# xmod_A.net
KiCad netlist of a schematic drawn in EAGLE
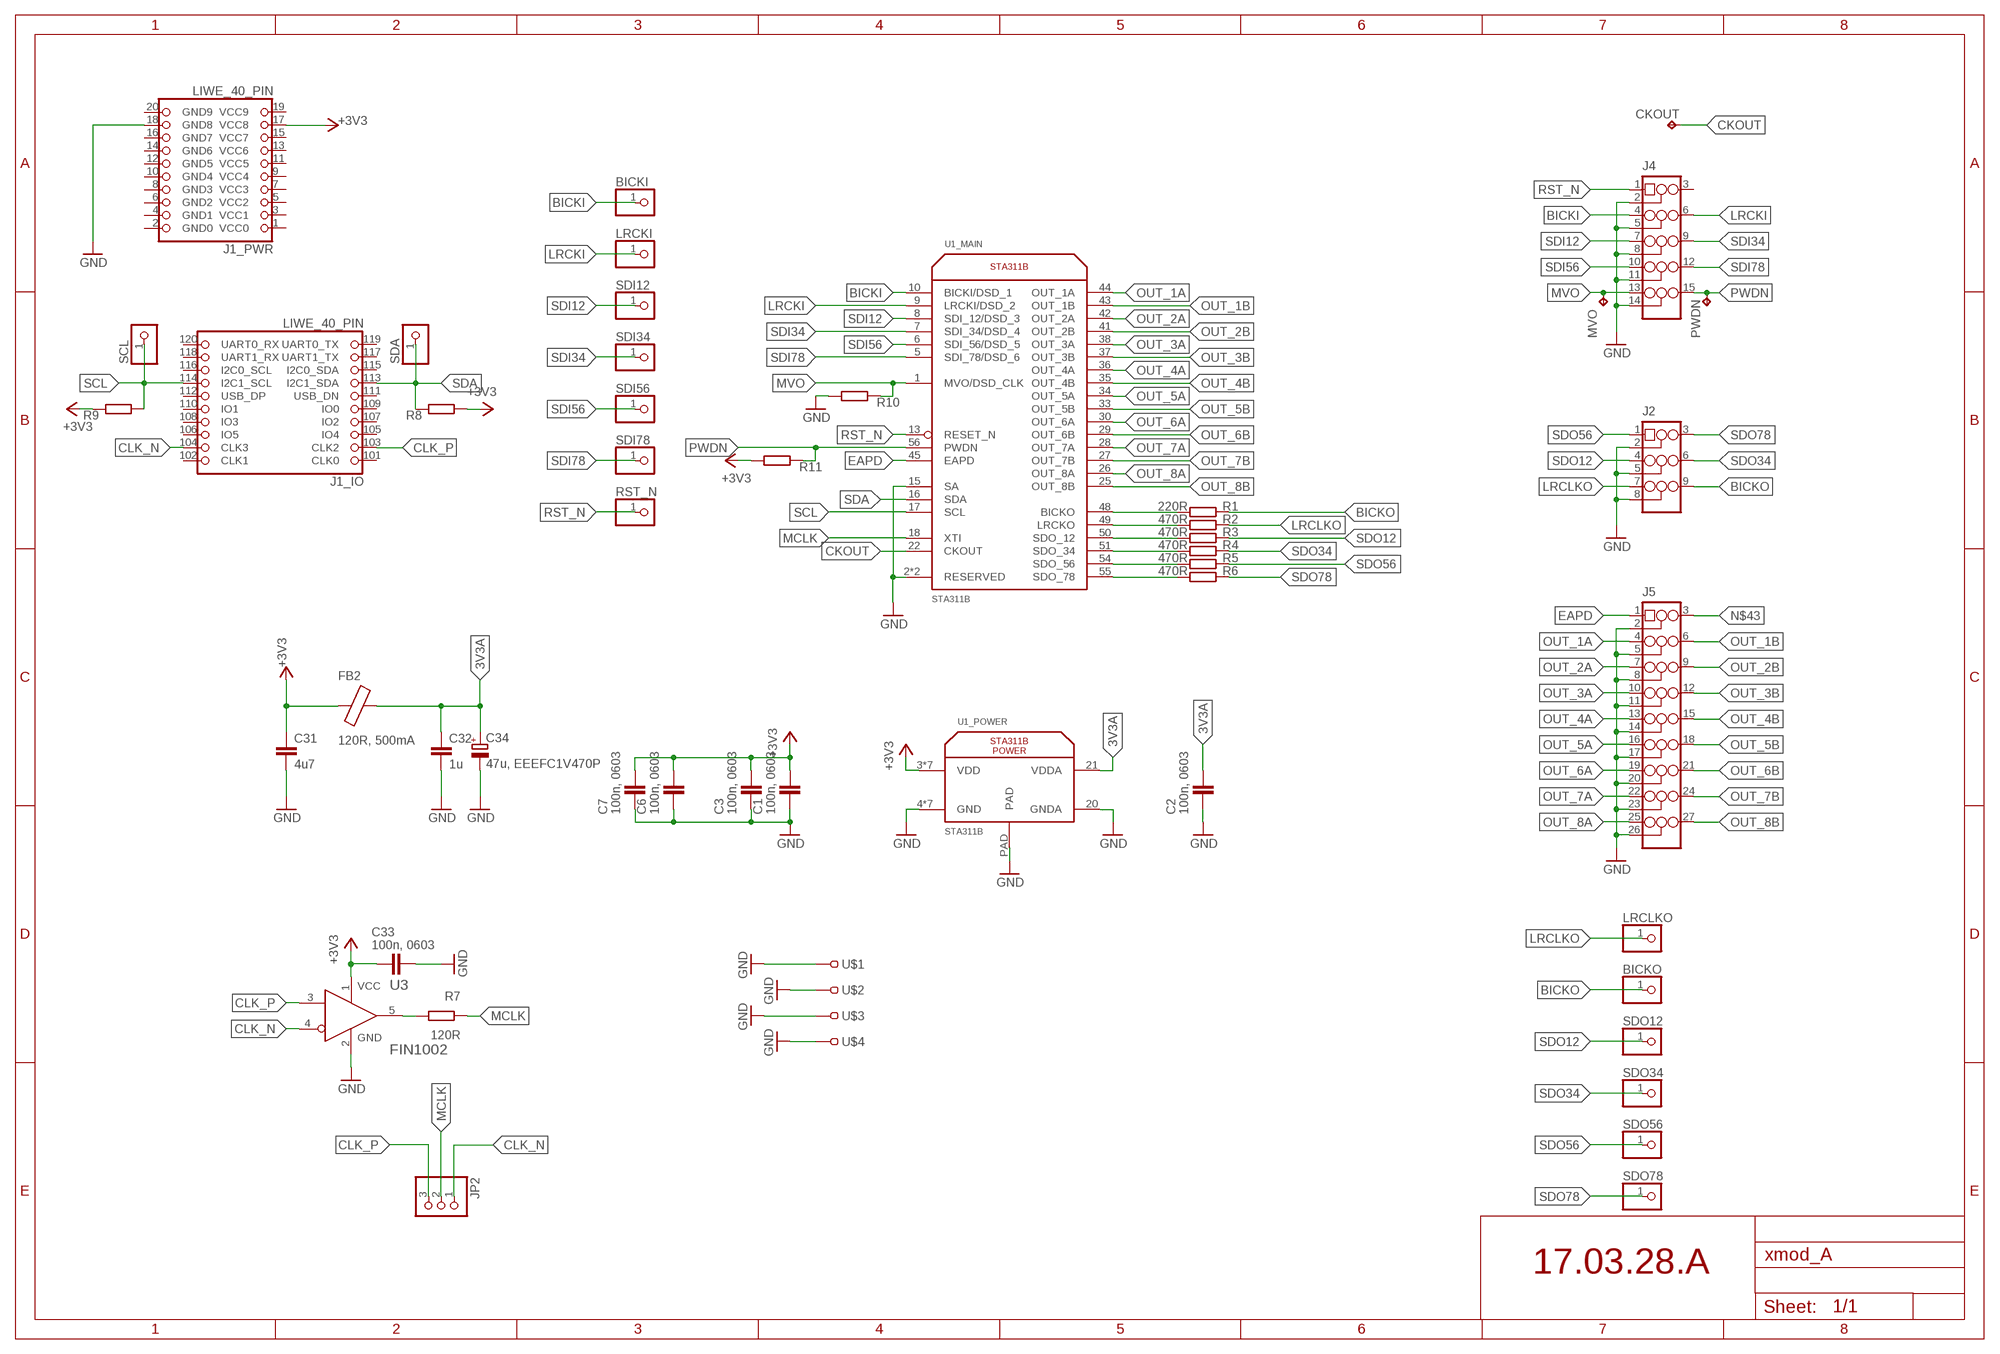
[diagram p0: schematic, sheet 1]

(export (version "E")
  (design (tool "Eeschema 10.0.6"))
  (components
    (comp (ref "BICKI")
      (value "PINHD-1X1")
      (footprint "eagle-import:1X01")
      (libsource (lib "eagle-import") (part "PINHD-1X1"))
    )
    (comp (ref "BICKO")
      (value "PINHD-1X1")
      (footprint "eagle-import:1X01")
      (libsource (lib "eagle-import") (part "PINHD-1X1"))
    )
    (comp (ref "C1")
      (value "100n, 0603")
      (footprint "eagle-import:C0603")
      (libsource (lib "eagle-import") (part "C-EUC0603"))
    )
    (comp (ref "C2")
      (value "100n, 0603")
      (footprint "eagle-import:C0603")
      (libsource (lib "eagle-import") (part "C-EUC0603"))
    )
    (comp (ref "C3")
      (value "100n, 0603")
      (footprint "eagle-import:C0603")
      (libsource (lib "eagle-import") (part "C-EUC0603"))
    )
    (comp (ref "C6")
      (value "100n, 0603")
      (footprint "eagle-import:C0603")
      (libsource (lib "eagle-import") (part "C-EUC0603"))
    )
    (comp (ref "C7")
      (value "100n, 0603")
      (footprint "eagle-import:C0603")
      (libsource (lib "eagle-import") (part "C-EUC0603"))
    )
    (comp (ref "C31")
      (value "4u7")
      (footprint "eagle-import:C0603K")
      (libsource (lib "eagle-import") (part "C-EUC0603K"))
    )
    (comp (ref "C32")
      (value "1u")
      (footprint "eagle-import:C0603K")
      (libsource (lib "eagle-import") (part "C-EUC0603K"))
    )
    (comp (ref "C33")
      (value "100n, 0603")
      (footprint "eagle-import:C0603")
      (libsource (lib "eagle-import") (part "C-EUC0603"))
    )
    (comp (ref "C34")
      (value "47u, EEEFC1V470P")
      (footprint "eagle-import:EEE-FC1V470P")
      (libsource (lib "eagle-import") (part "C-POL_E"))
    )
    (comp (ref "CKOUT")
      (value "TPTP14R")
      (footprint "eagle-import:TP14R")
      (libsource (lib "eagle-import") (part "TPTP14R"))
    )
    (comp (ref "FB2")
      (value "120R, 500mA")
      (footprint "eagle-import:L0603")
      (libsource (lib "eagle-import") (part "FB_0603"))
    )
    (comp (ref "J1")
      (value "LIWE_40_PIN")
      (footprint "eagle-import:LIWE_40_PIN_8X8")
      (libsource (lib "eagle-import") (part "LIWE_40_PIN"))
    )
    (comp (ref "J2")
      (value "PINHD-3X3/90")
      (footprint "eagle-import:3X03_90")
      (libsource (lib "eagle-import") (part "PINHD-3X3/90"))
    )
    (comp (ref "J4")
      (value "PINHD-3X5/90")
      (footprint "eagle-import:3X05_90")
      (libsource (lib "eagle-import") (part "PINHD-3X5/90"))
    )
    (comp (ref "J5")
      (value "PINHD-3X9/90")
      (footprint "eagle-import:3X9_90")
      (libsource (lib "eagle-import") (part "PINHD-3X9/90"))
    )
    (comp (ref "JP2")
      (value "PINHD-1X3")
      (footprint "eagle-import:1X03")
      (libsource (lib "eagle-import") (part "PINHD-1X3"))
    )
    (comp (ref "LRCKI")
      (value "PINHD-1X1")
      (footprint "eagle-import:1X01")
      (libsource (lib "eagle-import") (part "PINHD-1X1"))
    )
    (comp (ref "LRCLKO")
      (value "PINHD-1X1")
      (footprint "eagle-import:1X01")
      (libsource (lib "eagle-import") (part "PINHD-1X1"))
    )
    (comp (ref "MVO")
      (value "TPTP14R")
      (footprint "eagle-import:TP14R")
      (libsource (lib "eagle-import") (part "TPTP14R"))
    )
    (comp (ref "PWDN")
      (value "TPTP14R")
      (footprint "eagle-import:TP14R")
      (libsource (lib "eagle-import") (part "TPTP14R"))
    )
    (comp (ref "R1")
      (value "220R")
      (footprint "eagle-import:R0603")
      (libsource (lib "eagle-import") (part "R-EU_R0603"))
    )
    (comp (ref "R2")
      (value "470R")
      (footprint "eagle-import:R0603")
      (libsource (lib "eagle-import") (part "R-EU_R0603"))
    )
    (comp (ref "R3")
      (value "470R")
      (footprint "eagle-import:R0603")
      (libsource (lib "eagle-import") (part "R-EU_R0603"))
    )
    (comp (ref "R4")
      (value "470R")
      (footprint "eagle-import:R0603")
      (libsource (lib "eagle-import") (part "R-EU_R0603"))
    )
    (comp (ref "R5")
      (value "470R")
      (footprint "eagle-import:R0603")
      (libsource (lib "eagle-import") (part "R-EU_R0603"))
    )
    (comp (ref "R6")
      (value "470R")
      (footprint "eagle-import:R0603")
      (libsource (lib "eagle-import") (part "R-EU_R0603"))
    )
    (comp (ref "R7")
      (value "120R")
      (footprint "eagle-import:R0603")
      (libsource (lib "eagle-import") (part "R-EU_R0603"))
    )
    (comp (ref "R8")
      (value "R-EU_R0603")
      (footprint "eagle-import:R0603")
      (libsource (lib "eagle-import") (part "R-EU_R0603"))
    )
    (comp (ref "R9")
      (value "R-EU_R0603")
      (footprint "eagle-import:R0603")
      (libsource (lib "eagle-import") (part "R-EU_R0603"))
    )
    (comp (ref "R10")
      (value "R-EU_R0603")
      (footprint "eagle-import:R0603")
      (libsource (lib "eagle-import") (part "R-EU_R0603"))
    )
    (comp (ref "R11")
      (value "R-EU_R0603")
      (footprint "eagle-import:R0603")
      (libsource (lib "eagle-import") (part "R-EU_R0603"))
    )
    (comp (ref "RST_N")
      (value "PINHD-1X1")
      (footprint "eagle-import:1X01")
      (libsource (lib "eagle-import") (part "PINHD-1X1"))
    )
    (comp (ref "SCL")
      (value "PINHD-1X1")
      (footprint "eagle-import:1X01")
      (libsource (lib "eagle-import") (part "PINHD-1X1"))
    )
    (comp (ref "SDA")
      (value "PINHD-1X1")
      (footprint "eagle-import:1X01")
      (libsource (lib "eagle-import") (part "PINHD-1X1"))
    )
    (comp (ref "SDI12")
      (value "PINHD-1X1")
      (footprint "eagle-import:1X01")
      (libsource (lib "eagle-import") (part "PINHD-1X1"))
    )
    (comp (ref "SDI34")
      (value "PINHD-1X1")
      (footprint "eagle-import:1X01")
      (libsource (lib "eagle-import") (part "PINHD-1X1"))
    )
    (comp (ref "SDI56")
      (value "PINHD-1X1")
      (footprint "eagle-import:1X01")
      (libsource (lib "eagle-import") (part "PINHD-1X1"))
    )
    (comp (ref "SDI78")
      (value "PINHD-1X1")
      (footprint "eagle-import:1X01")
      (libsource (lib "eagle-import") (part "PINHD-1X1"))
    )
    (comp (ref "SDO12")
      (value "PINHD-1X1")
      (footprint "eagle-import:1X01")
      (libsource (lib "eagle-import") (part "PINHD-1X1"))
    )
    (comp (ref "SDO34")
      (value "PINHD-1X1")
      (footprint "eagle-import:1X01")
      (libsource (lib "eagle-import") (part "PINHD-1X1"))
    )
    (comp (ref "SDO56")
      (value "PINHD-1X1")
      (footprint "eagle-import:1X01")
      (libsource (lib "eagle-import") (part "PINHD-1X1"))
    )
    (comp (ref "SDO78")
      (value "PINHD-1X1")
      (footprint "eagle-import:1X01")
      (libsource (lib "eagle-import") (part "PINHD-1X1"))
    )
    (comp (ref "U$1")
      (value "TEST-22-MULTICOMP")
      (footprint "eagle-import:TEST_1MM")
      (libsource (lib "eagle-import") (part "TEST-22-MULTICOMP"))
    )
    (comp (ref "U$2")
      (value "TEST-22-MULTICOMP")
      (footprint "eagle-import:TEST_1MM")
      (libsource (lib "eagle-import") (part "TEST-22-MULTICOMP"))
    )
    (comp (ref "U$3")
      (value "TEST-22-MULTICOMP")
      (footprint "eagle-import:TEST_1MM")
      (libsource (lib "eagle-import") (part "TEST-22-MULTICOMP"))
    )
    (comp (ref "U$4")
      (value "TEST-22-MULTICOMP")
      (footprint "eagle-import:TEST_1MM")
      (libsource (lib "eagle-import") (part "TEST-22-MULTICOMP"))
    )
    (comp (ref "U1")
      (value "STA311B")
      (footprint "eagle-import:VFQFPN_56_8X8")
      (libsource (lib "eagle-import") (part "STA311B"))
    )
    (comp (ref "U3")
      (value "FIN1002")
      (footprint "eagle-import:SOT95P280X140-5N")
      (libsource (lib "eagle-import") (part "FIN1002"))
    )
  )
  (nets
    (net (code "1") (name "+3V3") (class "Default")
      (node (ref "C1") (pin "1") (pinfunction "1_1") (pintype "passive"))
      (node (ref "C3") (pin "1") (pinfunction "1_1") (pintype "passive"))
      (node (ref "C31") (pin "1") (pinfunction "1_1") (pintype "passive"))
      (node (ref "C33") (pin "2") (pinfunction "2_2") (pintype "passive"))
      (node (ref "C6") (pin "1") (pinfunction "1_1") (pintype "passive"))
      (node (ref "C7") (pin "1") (pinfunction "1_1") (pintype "passive"))
      (node (ref "FB2") (pin "2") (pinfunction "P$2_2") (pintype "bidirectional"))
      (node (ref "J1") (pin "17") (pinfunction "VCC8_17") (pintype "passive"))
      (node (ref "R11") (pin "2") (pinfunction "2_2") (pintype "passive"))
      (node (ref "R8") (pin "1") (pinfunction "1_1") (pintype "passive"))
      (node (ref "R9") (pin "2") (pinfunction "2_2") (pintype "passive"))
      (node (ref "U1") (pin "11") (pinfunction "VDD_11") (pintype "bidirectional"))
      (node (ref "U1") (pin "24") (pinfunction "VDD_24") (pintype "bidirectional"))
      (node (ref "U1") (pin "3") (pinfunction "VDD_3") (pintype "bidirectional"))
      (node (ref "U1") (pin "31") (pinfunction "VDD_31") (pintype "bidirectional"))
      (node (ref "U1") (pin "39") (pinfunction "VDD_39") (pintype "bidirectional"))
      (node (ref "U1") (pin "46") (pinfunction "VDD_46") (pintype "bidirectional"))
      (node (ref "U1") (pin "52") (pinfunction "VDD_52") (pintype "bidirectional"))
      (node (ref "U3") (pin "1") (pinfunction "VCC_1") (pintype "power_in"))
    )
    (net (code "2") (name "3V3A") (class "Default")
      (node (ref "C2") (pin "1") (pinfunction "1_1") (pintype "passive"))
      (node (ref "C32") (pin "1") (pinfunction "1_1") (pintype "passive"))
      (node (ref "C34") (pin "1") (pinfunction "+_1") (pintype "passive"))
      (node (ref "FB2") (pin "1") (pinfunction "P$1_1") (pintype "bidirectional"))
      (node (ref "U1") (pin "21") (pinfunction "VDDA_21") (pintype "bidirectional"))
    )
    (net (code "3") (name "BICKI") (class "Default")
      (node (ref "BICKI") (pin "1") (pinfunction "1_1") (pintype "passive"))
      (node (ref "J4") (pin "4") (pinfunction "4_4") (pintype "passive"))
      (node (ref "U1") (pin "10") (pinfunction "BICKI/DSD_1_10") (pintype "bidirectional"))
    )
    (net (code "4") (name "BICKO") (class "Default")
      (node (ref "BICKO") (pin "1") (pinfunction "1_1") (pintype "passive"))
      (node (ref "J2") (pin "9") (pinfunction "9_9") (pintype "passive"))
      (node (ref "R1") (pin "2") (pinfunction "2_2") (pintype "passive"))
    )
    (net (code "5") (name "CKOUT") (class "Default")
      (node (ref "CKOUT") (pin "TP") (pinfunction "TP_TP") (pintype "input"))
      (node (ref "U1") (pin "22") (pinfunction "CKOUT_22") (pintype "bidirectional"))
    )
    (net (code "6") (name "CLK_N") (class "Default")
      (node (ref "J1") (pin "104") (pinfunction "CLK3_104") (pintype "passive"))
      (node (ref "JP2") (pin "1") (pinfunction "1_1") (pintype "passive"))
      (node (ref "U3") (pin "4") (pinfunction "RIN-_4") (pintype "input"))
    )
    (net (code "7") (name "CLK_P") (class "Default")
      (node (ref "J1") (pin "103") (pinfunction "CLK2_103") (pintype "passive"))
      (node (ref "JP2") (pin "3") (pinfunction "3_3") (pintype "passive"))
      (node (ref "U3") (pin "3") (pinfunction "RIN+_3") (pintype "input"))
    )
    (net (code "8") (name "EAPD") (class "Default")
      (node (ref "J5") (pin "1") (pinfunction "1_1") (pintype "passive"))
      (node (ref "U1") (pin "45") (pinfunction "EAPD_45") (pintype "bidirectional"))
    )
    (net (code "9") (name "GND") (class "Default")
      (node (ref "C1") (pin "2") (pinfunction "2_2") (pintype "passive"))
      (node (ref "C2") (pin "2") (pinfunction "2_2") (pintype "passive"))
      (node (ref "C3") (pin "2") (pinfunction "2_2") (pintype "passive"))
      (node (ref "C31") (pin "2") (pinfunction "2_2") (pintype "passive"))
      (node (ref "C32") (pin "2") (pinfunction "2_2") (pintype "passive"))
      (node (ref "C33") (pin "1") (pinfunction "1_1") (pintype "passive"))
      (node (ref "C34") (pin "2") (pinfunction "-_2") (pintype "passive"))
      (node (ref "C6") (pin "2") (pinfunction "2_2") (pintype "passive"))
      (node (ref "C7") (pin "2") (pinfunction "2_2") (pintype "passive"))
      (node (ref "J1") (pin "18") (pinfunction "GND8_18") (pintype "passive"))
      (node (ref "J2") (pin "2") (pinfunction "2_2") (pintype "passive"))
      (node (ref "J2") (pin "5") (pinfunction "5_5") (pintype "passive"))
      (node (ref "J2") (pin "8") (pinfunction "8_8") (pintype "passive"))
      (node (ref "J4") (pin "11") (pinfunction "11_11") (pintype "passive"))
      (node (ref "J4") (pin "14") (pinfunction "14_14") (pintype "passive"))
      (node (ref "J4") (pin "2") (pinfunction "2_2") (pintype "passive"))
      (node (ref "J4") (pin "5") (pinfunction "5_5") (pintype "passive"))
      (node (ref "J4") (pin "8") (pinfunction "8_8") (pintype "passive"))
      (node (ref "J5") (pin "11") (pinfunction "11_11") (pintype "passive"))
      (node (ref "J5") (pin "14") (pinfunction "14_14") (pintype "passive"))
      (node (ref "J5") (pin "17") (pinfunction "17_17") (pintype "passive"))
      (node (ref "J5") (pin "2") (pinfunction "2_2") (pintype "passive"))
      (node (ref "J5") (pin "20") (pinfunction "20_20") (pintype "passive"))
      (node (ref "J5") (pin "23") (pinfunction "23_23") (pintype "passive"))
      (node (ref "J5") (pin "26") (pinfunction "26_26") (pintype "passive"))
      (node (ref "J5") (pin "5") (pinfunction "5_5") (pintype "passive"))
      (node (ref "J5") (pin "8") (pinfunction "8_8") (pintype "passive"))
      (node (ref "R10") (pin "2") (pinfunction "2_2") (pintype "passive"))
      (node (ref "U$1") (pin "1") (pinfunction "1_1") (pintype "passive"))
      (node (ref "U$2") (pin "1") (pinfunction "1_1") (pintype "passive"))
      (node (ref "U$3") (pin "1") (pinfunction "1_1") (pintype "passive"))
      (node (ref "U$4") (pin "1") (pinfunction "1_1") (pintype "passive"))
      (node (ref "U1") (pin "12") (pinfunction "GND_12") (pintype "bidirectional"))
      (node (ref "U1") (pin "14") (pinfunction "RESERVED_14") (pintype "bidirectional"))
      (node (ref "U1") (pin "15") (pinfunction "SA_15") (pintype "bidirectional"))
      (node (ref "U1") (pin "2") (pinfunction "RESERVED_2") (pintype "bidirectional"))
      (node (ref "U1") (pin "20") (pinfunction "GNDA_20") (pintype "bidirectional"))
      (node (ref "U1") (pin "23") (pinfunction "GND_23") (pintype "bidirectional"))
      (node (ref "U1") (pin "32") (pinfunction "GND_32") (pintype "bidirectional"))
      (node (ref "U1") (pin "4") (pinfunction "GND_4") (pintype "bidirectional"))
      (node (ref "U1") (pin "40") (pinfunction "GND_40") (pintype "bidirectional"))
      (node (ref "U1") (pin "47") (pinfunction "GND_47") (pintype "bidirectional"))
      (node (ref "U1") (pin "53") (pinfunction "GND_53") (pintype "bidirectional"))
      (node (ref "U1") (pin "PAD") (pinfunction "PAD_PAD") (pintype "bidirectional"))
      (node (ref "U3") (pin "2") (pinfunction "GND_2") (pintype "passive"))
    )
    (net (code "10") (name "LRCKI") (class "Default")
      (node (ref "J4") (pin "6") (pinfunction "6_6") (pintype "passive"))
      (node (ref "LRCKI") (pin "1") (pinfunction "1_1") (pintype "passive"))
      (node (ref "U1") (pin "9") (pinfunction "LRCKI/DSD_2_9") (pintype "bidirectional"))
    )
    (net (code "11") (name "LRCLKO") (class "Default")
      (node (ref "J2") (pin "7") (pinfunction "7_7") (pintype "passive"))
      (node (ref "LRCLKO") (pin "1") (pinfunction "1_1") (pintype "passive"))
      (node (ref "R2") (pin "2") (pinfunction "2_2") (pintype "passive"))
    )
    (net (code "12") (name "MCLK") (class "Default")
      (node (ref "JP2") (pin "2") (pinfunction "2_2") (pintype "passive"))
      (node (ref "R7") (pin "1") (pinfunction "1_1") (pintype "passive"))
      (node (ref "U1") (pin "18") (pinfunction "XTI_18") (pintype "bidirectional"))
    )
    (net (code "13") (name "MVO") (class "Default")
      (node (ref "J4") (pin "13") (pinfunction "13_13") (pintype "passive"))
      (node (ref "MVO") (pin "TP") (pinfunction "TP_TP") (pintype "input"))
      (node (ref "R10") (pin "1") (pinfunction "1_1") (pintype "passive"))
      (node (ref "U1") (pin "1") (pinfunction "MVO/DSD_CLK_1") (pintype "bidirectional"))
    )
    (net (code "14") (name "N$43") (class "Default")
      (node (ref "J5") (pin "3") (pinfunction "3_3") (pintype "passive"))
    )
    (net (code "15") (name "Net-(U1A-BICKO)") (class "Default")
      (node (ref "R1") (pin "1") (pinfunction "1_1") (pintype "passive"))
      (node (ref "U1") (pin "48") (pinfunction "BICKO_48") (pintype "bidirectional"))
    )
    (net (code "16") (name "Net-(U1A-LRCKO)") (class "Default")
      (node (ref "R2") (pin "1") (pinfunction "1_1") (pintype "passive"))
      (node (ref "U1") (pin "49") (pinfunction "LRCKO_49") (pintype "bidirectional"))
    )
    (net (code "17") (name "Net-(U1A-SDO_12)") (class "Default")
      (node (ref "R3") (pin "1") (pinfunction "1_1") (pintype "passive"))
      (node (ref "U1") (pin "50") (pinfunction "SDO_12_50") (pintype "bidirectional"))
    )
    (net (code "18") (name "Net-(U1A-SDO_34)") (class "Default")
      (node (ref "R4") (pin "1") (pinfunction "1_1") (pintype "passive"))
      (node (ref "U1") (pin "51") (pinfunction "SDO_34_51") (pintype "bidirectional"))
    )
    (net (code "19") (name "Net-(U1A-SDO_56)") (class "Default")
      (node (ref "R5") (pin "1") (pinfunction "1_1") (pintype "passive"))
      (node (ref "U1") (pin "54") (pinfunction "SDO_56_54") (pintype "bidirectional"))
    )
    (net (code "20") (name "Net-(U1A-SDO_78)") (class "Default")
      (node (ref "R6") (pin "1") (pinfunction "1_1") (pintype "passive"))
      (node (ref "U1") (pin "55") (pinfunction "SDO_78_55") (pintype "bidirectional"))
    )
    (net (code "21") (name "Net-(U3-ROUT)") (class "Default")
      (node (ref "R7") (pin "2") (pinfunction "2_2") (pintype "passive"))
      (node (ref "U3") (pin "5") (pinfunction "ROUT_5") (pintype "output"))
    )
    (net (code "22") (name "OUT_1A") (class "Default")
      (node (ref "J5") (pin "4") (pinfunction "4_4") (pintype "passive"))
      (node (ref "U1") (pin "44") (pinfunction "OUT_1A_44") (pintype "bidirectional"))
    )
    (net (code "23") (name "OUT_1B") (class "Default")
      (node (ref "J5") (pin "6") (pinfunction "6_6") (pintype "passive"))
      (node (ref "U1") (pin "43") (pinfunction "OUT_1B_43") (pintype "bidirectional"))
    )
    (net (code "24") (name "OUT_2A") (class "Default")
      (node (ref "J5") (pin "7") (pinfunction "7_7") (pintype "passive"))
      (node (ref "U1") (pin "42") (pinfunction "OUT_2A_42") (pintype "bidirectional"))
    )
    (net (code "25") (name "OUT_2B") (class "Default")
      (node (ref "J5") (pin "9") (pinfunction "9_9") (pintype "passive"))
      (node (ref "U1") (pin "41") (pinfunction "OUT_2B_41") (pintype "bidirectional"))
    )
    (net (code "26") (name "OUT_3A") (class "Default")
      (node (ref "J5") (pin "10") (pinfunction "10_10") (pintype "passive"))
      (node (ref "U1") (pin "38") (pinfunction "OUT_3A_38") (pintype "bidirectional"))
    )
    (net (code "27") (name "OUT_3B") (class "Default")
      (node (ref "J5") (pin "12") (pinfunction "12_12") (pintype "passive"))
      (node (ref "U1") (pin "37") (pinfunction "OUT_3B_37") (pintype "bidirectional"))
    )
    (net (code "28") (name "OUT_4A") (class "Default")
      (node (ref "J5") (pin "13") (pinfunction "13_13") (pintype "passive"))
      (node (ref "U1") (pin "36") (pinfunction "OUT_4A_36") (pintype "bidirectional"))
    )
    (net (code "29") (name "OUT_4B") (class "Default")
      (node (ref "J5") (pin "15") (pinfunction "15_15") (pintype "passive"))
      (node (ref "U1") (pin "35") (pinfunction "OUT_4B_35") (pintype "bidirectional"))
    )
    (net (code "30") (name "OUT_5A") (class "Default")
      (node (ref "J5") (pin "16") (pinfunction "16_16") (pintype "passive"))
      (node (ref "U1") (pin "34") (pinfunction "OUT_5A_34") (pintype "bidirectional"))
    )
    (net (code "31") (name "OUT_5B") (class "Default")
      (node (ref "J5") (pin "18") (pinfunction "18_18") (pintype "passive"))
      (node (ref "U1") (pin "33") (pinfunction "OUT_5B_33") (pintype "bidirectional"))
    )
    (net (code "32") (name "OUT_6A") (class "Default")
      (node (ref "J5") (pin "19") (pinfunction "19_19") (pintype "passive"))
      (node (ref "U1") (pin "30") (pinfunction "OUT_6A_30") (pintype "bidirectional"))
    )
    (net (code "33") (name "OUT_6B") (class "Default")
      (node (ref "J5") (pin "21") (pinfunction "21_21") (pintype "passive"))
      (node (ref "U1") (pin "29") (pinfunction "OUT_6B_29") (pintype "bidirectional"))
    )
    (net (code "34") (name "OUT_7A") (class "Default")
      (node (ref "J5") (pin "22") (pinfunction "22_22") (pintype "passive"))
      (node (ref "U1") (pin "28") (pinfunction "OUT_7A_28") (pintype "bidirectional"))
    )
    (net (code "35") (name "OUT_7B") (class "Default")
      (node (ref "J5") (pin "24") (pinfunction "24_24") (pintype "passive"))
      (node (ref "U1") (pin "27") (pinfunction "OUT_7B_27") (pintype "bidirectional"))
    )
    (net (code "36") (name "OUT_8A") (class "Default")
      (node (ref "J5") (pin "25") (pinfunction "25_25") (pintype "passive"))
      (node (ref "U1") (pin "26") (pinfunction "OUT_8A_26") (pintype "bidirectional"))
    )
    (net (code "37") (name "OUT_8B") (class "Default")
      (node (ref "J5") (pin "27") (pinfunction "27_27") (pintype "passive"))
      (node (ref "U1") (pin "25") (pinfunction "OUT_8B_25") (pintype "bidirectional"))
    )
    (net (code "38") (name "PWDN") (class "Default")
      (node (ref "J4") (pin "15") (pinfunction "15_15") (pintype "passive"))
      (node (ref "PWDN") (pin "TP") (pinfunction "TP_TP") (pintype "input"))
      (node (ref "R11") (pin "1") (pinfunction "1_1") (pintype "passive"))
      (node (ref "U1") (pin "56") (pinfunction "PWDN_56") (pintype "bidirectional"))
    )
    (net (code "39") (name "RST_N") (class "Default")
      (node (ref "J4") (pin "1") (pinfunction "1_1") (pintype "passive"))
      (node (ref "RST_N") (pin "1") (pinfunction "1_1") (pintype "passive"))
      (node (ref "U1") (pin "13") (pinfunction "RESET_N_13") (pintype "input"))
    )
    (net (code "40") (name "SCL") (class "Default")
      (node (ref "J1") (pin "114") (pinfunction "I2C1_SCL_114") (pintype "passive"))
      (node (ref "R9") (pin "1") (pinfunction "1_1") (pintype "passive"))
      (node (ref "SCL") (pin "1") (pinfunction "1_1") (pintype "passive"))
      (node (ref "U1") (pin "17") (pinfunction "SCL_17") (pintype "bidirectional"))
    )
    (net (code "41") (name "SDA") (class "Default")
      (node (ref "J1") (pin "113") (pinfunction "I2C1_SDA_113") (pintype "passive"))
      (node (ref "R8") (pin "2") (pinfunction "2_2") (pintype "passive"))
      (node (ref "SDA") (pin "1") (pinfunction "1_1") (pintype "passive"))
      (node (ref "U1") (pin "16") (pinfunction "SDA_16") (pintype "bidirectional"))
    )
    (net (code "42") (name "SDI12") (class "Default")
      (node (ref "J4") (pin "7") (pinfunction "7_7") (pintype "passive"))
      (node (ref "SDI12") (pin "1") (pinfunction "1_1") (pintype "passive"))
      (node (ref "U1") (pin "8") (pinfunction "SDI_12/DSD_3_8") (pintype "bidirectional"))
    )
    (net (code "43") (name "SDI34") (class "Default")
      (node (ref "J4") (pin "9") (pinfunction "9_9") (pintype "passive"))
      (node (ref "SDI34") (pin "1") (pinfunction "1_1") (pintype "passive"))
      (node (ref "U1") (pin "7") (pinfunction "SDI_34/DSD_4_7") (pintype "bidirectional"))
    )
    (net (code "44") (name "SDI56") (class "Default")
      (node (ref "J4") (pin "10") (pinfunction "10_10") (pintype "passive"))
      (node (ref "SDI56") (pin "1") (pinfunction "1_1") (pintype "passive"))
      (node (ref "U1") (pin "6") (pinfunction "SDI_56/DSD_5_6") (pintype "bidirectional"))
    )
    (net (code "45") (name "SDI78") (class "Default")
      (node (ref "J4") (pin "12") (pinfunction "12_12") (pintype "passive"))
      (node (ref "SDI78") (pin "1") (pinfunction "1_1") (pintype "passive"))
      (node (ref "U1") (pin "5") (pinfunction "SDI_78/DSD_6_5") (pintype "bidirectional"))
    )
    (net (code "46") (name "SDO12") (class "Default")
      (node (ref "J2") (pin "4") (pinfunction "4_4") (pintype "passive"))
      (node (ref "R3") (pin "2") (pinfunction "2_2") (pintype "passive"))
      (node (ref "SDO12") (pin "1") (pinfunction "1_1") (pintype "passive"))
    )
    (net (code "47") (name "SDO34") (class "Default")
      (node (ref "J2") (pin "6") (pinfunction "6_6") (pintype "passive"))
      (node (ref "R4") (pin "2") (pinfunction "2_2") (pintype "passive"))
      (node (ref "SDO34") (pin "1") (pinfunction "1_1") (pintype "passive"))
    )
    (net (code "48") (name "SDO56") (class "Default")
      (node (ref "J2") (pin "1") (pinfunction "1_1") (pintype "passive"))
      (node (ref "R5") (pin "2") (pinfunction "2_2") (pintype "passive"))
      (node (ref "SDO56") (pin "1") (pinfunction "1_1") (pintype "passive"))
    )
    (net (code "49") (name "SDO78") (class "Default")
      (node (ref "J2") (pin "3") (pinfunction "3_3") (pintype "passive"))
      (node (ref "R6") (pin "2") (pinfunction "2_2") (pintype "passive"))
      (node (ref "SDO78") (pin "1") (pinfunction "1_1") (pintype "passive"))
    )
    (net (code "50") (name "unconnected-(J1A-CLK0-Pad101)") (class "Default")
      (node (ref "J1") (pin "101") (pinfunction "CLK0_101") (pintype "passive"))
    )
    (net (code "51") (name "unconnected-(J1A-CLK1-Pad102)") (class "Default")
      (node (ref "J1") (pin "102") (pinfunction "CLK1_102") (pintype "passive"))
    )
    (net (code "52") (name "unconnected-(J1A-I2C0_SCL-Pad116)") (class "Default")
      (node (ref "J1") (pin "116") (pinfunction "I2C0_SCL_116") (pintype "passive"))
    )
    (net (code "53") (name "unconnected-(J1A-I2C0_SDA-Pad115)") (class "Default")
      (node (ref "J1") (pin "115") (pinfunction "I2C0_SDA_115") (pintype "passive"))
    )
    (net (code "54") (name "unconnected-(J1A-IO0-Pad109)") (class "Default")
      (node (ref "J1") (pin "109") (pinfunction "IO0_109") (pintype "passive"))
    )
    (net (code "55") (name "unconnected-(J1A-IO1-Pad110)") (class "Default")
      (node (ref "J1") (pin "110") (pinfunction "IO1_110") (pintype "passive"))
    )
    (net (code "56") (name "unconnected-(J1A-IO2-Pad107)") (class "Default")
      (node (ref "J1") (pin "107") (pinfunction "IO2_107") (pintype "passive"))
    )
    (net (code "57") (name "unconnected-(J1A-IO3-Pad108)") (class "Default")
      (node (ref "J1") (pin "108") (pinfunction "IO3_108") (pintype "passive"))
    )
    (net (code "58") (name "unconnected-(J1A-IO4-Pad105)") (class "Default")
      (node (ref "J1") (pin "105") (pinfunction "IO4_105") (pintype "passive"))
    )
    (net (code "59") (name "unconnected-(J1A-IO5-Pad106)") (class "Default")
      (node (ref "J1") (pin "106") (pinfunction "IO5_106") (pintype "passive"))
    )
    (net (code "60") (name "unconnected-(J1A-UART0_RX-Pad120)") (class "Default")
      (node (ref "J1") (pin "120") (pinfunction "UART0_RX_120") (pintype "passive"))
    )
    (net (code "61") (name "unconnected-(J1A-UART0_TX-Pad119)") (class "Default")
      (node (ref "J1") (pin "119") (pinfunction "UART0_TX_119") (pintype "passive"))
    )
    (net (code "62") (name "unconnected-(J1A-UART1_RX-Pad118)") (class "Default")
      (node (ref "J1") (pin "118") (pinfunction "UART1_RX_118") (pintype "passive"))
    )
    (net (code "63") (name "unconnected-(J1A-UART1_TX-Pad117)") (class "Default")
      (node (ref "J1") (pin "117") (pinfunction "UART1_TX_117") (pintype "passive"))
    )
    (net (code "64") (name "unconnected-(J1A-USB_DN-Pad111)") (class "Default")
      (node (ref "J1") (pin "111") (pinfunction "USB_DN_111") (pintype "passive"))
    )
    (net (code "65") (name "unconnected-(J1A-USB_DP-Pad112)") (class "Default")
      (node (ref "J1") (pin "112") (pinfunction "USB_DP_112") (pintype "passive"))
    )
    (net (code "66") (name "unconnected-(J1B-GND0-Pad2)") (class "Default")
      (node (ref "J1") (pin "2") (pinfunction "GND0_2") (pintype "passive"))
    )
    (net (code "67") (name "unconnected-(J1B-GND1-Pad4)") (class "Default")
      (node (ref "J1") (pin "4") (pinfunction "GND1_4") (pintype "passive"))
    )
    (net (code "68") (name "unconnected-(J1B-GND2-Pad6)") (class "Default")
      (node (ref "J1") (pin "6") (pinfunction "GND2_6") (pintype "passive"))
    )
    (net (code "69") (name "unconnected-(J1B-GND3-Pad8)") (class "Default")
      (node (ref "J1") (pin "8") (pinfunction "GND3_8") (pintype "passive"))
    )
    (net (code "70") (name "unconnected-(J1B-GND4-Pad10)") (class "Default")
      (node (ref "J1") (pin "10") (pinfunction "GND4_10") (pintype "passive"))
    )
    (net (code "71") (name "unconnected-(J1B-GND5-Pad12)") (class "Default")
      (node (ref "J1") (pin "12") (pinfunction "GND5_12") (pintype "passive"))
    )
    (net (code "72") (name "unconnected-(J1B-GND6-Pad14)") (class "Default")
      (node (ref "J1") (pin "14") (pinfunction "GND6_14") (pintype "passive"))
    )
    (net (code "73") (name "unconnected-(J1B-GND7-Pad16)") (class "Default")
      (node (ref "J1") (pin "16") (pinfunction "GND7_16") (pintype "passive"))
    )
    (net (code "74") (name "unconnected-(J1B-GND9-Pad20)") (class "Default")
      (node (ref "J1") (pin "20") (pinfunction "GND9_20") (pintype "passive"))
    )
    (net (code "75") (name "unconnected-(J1B-VCC0-Pad1)") (class "Default")
      (node (ref "J1") (pin "1") (pinfunction "VCC0_1") (pintype "passive"))
    )
    (net (code "76") (name "unconnected-(J1B-VCC1-Pad3)") (class "Default")
      (node (ref "J1") (pin "3") (pinfunction "VCC1_3") (pintype "passive"))
    )
    (net (code "77") (name "unconnected-(J1B-VCC2-Pad5)") (class "Default")
      (node (ref "J1") (pin "5") (pinfunction "VCC2_5") (pintype "passive"))
    )
    (net (code "78") (name "unconnected-(J1B-VCC3-Pad7)") (class "Default")
      (node (ref "J1") (pin "7") (pinfunction "VCC3_7") (pintype "passive"))
    )
    (net (code "79") (name "unconnected-(J1B-VCC4-Pad9)") (class "Default")
      (node (ref "J1") (pin "9") (pinfunction "VCC4_9") (pintype "passive"))
    )
    (net (code "80") (name "unconnected-(J1B-VCC5-Pad11)") (class "Default")
      (node (ref "J1") (pin "11") (pinfunction "VCC5_11") (pintype "passive"))
    )
    (net (code "81") (name "unconnected-(J1B-VCC6-Pad13)") (class "Default")
      (node (ref "J1") (pin "13") (pinfunction "VCC6_13") (pintype "passive"))
    )
    (net (code "82") (name "unconnected-(J1B-VCC7-Pad15)") (class "Default")
      (node (ref "J1") (pin "15") (pinfunction "VCC7_15") (pintype "passive"))
    )
    (net (code "83") (name "unconnected-(J1B-VCC9-Pad19)") (class "Default")
      (node (ref "J1") (pin "19") (pinfunction "VCC9_19") (pintype "passive"))
    )
    (net (code "84") (name "unconnected-(J4-Pad3)") (class "Default")
      (node (ref "J4") (pin "3") (pinfunction "3_3") (pintype "passive"))
    )
  )
)
